# IR.net
KiCad netlist of a schematic drawn in Altium Designer
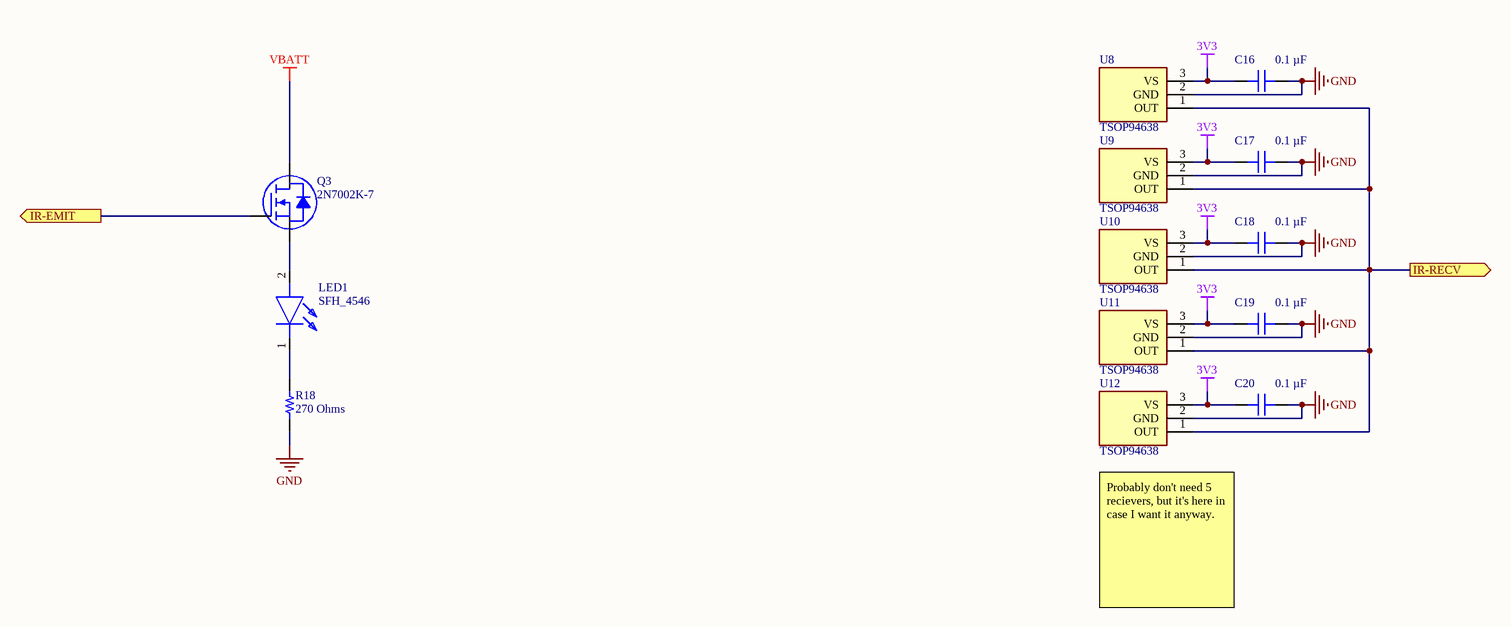
[diagram p0: IR.SchDoc]

(export (version "E")
  (design (tool "Eeschema 10.0.6"))
  (components
    (comp (ref "C16")
      (value "0.1 µF")
      (footprint "CAP 0805_2012")
      (description "CAP CER 0.1UF 25V X7R 0805")
      (fields
        (field (name "PART NUMBER") "0805B104K250CT")
        (field (name "CAPACITANCE") "0.1 µF")
        (field (name "MANUFACTURER") "Walsin Technology Corporation")
      )
      (libsource (lib "dblib") (part "Capacitor"))
    )
    (comp (ref "C17")
      (value "0.1 µF")
      (footprint "CAP 0805_2012")
      (description "CAP CER 0.1UF 25V X7R 0805")
      (fields
        (field (name "PART NUMBER") "0805B104K250CT")
        (field (name "CAPACITANCE") "0.1 µF")
        (field (name "MANUFACTURER") "Walsin Technology Corporation")
      )
      (libsource (lib "dblib") (part "Capacitor"))
    )
    (comp (ref "C18")
      (value "0.1 µF")
      (footprint "CAP 0805_2012")
      (description "CAP CER 0.1UF 25V X7R 0805")
      (fields
        (field (name "PART NUMBER") "0805B104K250CT")
        (field (name "CAPACITANCE") "0.1 µF")
        (field (name "MANUFACTURER") "Walsin Technology Corporation")
      )
      (libsource (lib "dblib") (part "Capacitor"))
    )
    (comp (ref "C19")
      (value "0.1 µF")
      (footprint "CAP 0805_2012")
      (description "CAP CER 0.1UF 25V X7R 0805")
      (fields
        (field (name "PART NUMBER") "0805B104K250CT")
        (field (name "CAPACITANCE") "0.1 µF")
        (field (name "MANUFACTURER") "Walsin Technology Corporation")
      )
      (libsource (lib "dblib") (part "Capacitor"))
    )
    (comp (ref "C20")
      (value "0.1 µF")
      (footprint "CAP 0805_2012")
      (description "CAP CER 0.1UF 25V X7R 0805")
      (fields
        (field (name "PART NUMBER") "0805B104K250CT")
        (field (name "CAPACITANCE") "0.1 µF")
        (field (name "MANUFACTURER") "Walsin Technology Corporation")
      )
      (libsource (lib "dblib") (part "Capacitor"))
    )
    (comp (ref "LED1")
      (value "SFH_4546")
      (footprint "SamacSys:SFH_4556P")
      (description "LED")
      (fields
        (field (name "MANUFACTURER_PART_NUMBER") "SFH 4546")
        (field (name "MOUSER PART NUMBER") "720-SFH4546")
      )
      (libsource (lib "*") (part "SFH_4546"))
    )
    (comp (ref "Q3")
      (value "2N7002K-7")
      (footprint "DIODES SOT-23-3")
      (description "MOSFET N-CH 60V 380MA SOT23-3")
      (fields (field (name "MANUFACTURER") "Diodes Incorporated"))
      (libsource (lib "dblib") (part "DIODES INC MOSFET N-CH SOT-23-3"))
    )
    (comp (ref "R18")
      (value "270 Ohms")
      (footprint "RES 0805_2012")
      (description "RES SMD 270 OHM 1% 1/8W 0805")
      (fields
        (field (name "PART NUMBER") "CRG0805F270R")
        (field (name "MANUFACTURER") "TE Connectivity Passive Product")
      )
      (libsource (lib "dblib") (part "Resistor"))
    )
    (comp (ref "U8")
      (value "TSOP94638")
      (footprint "SamacSys:TSOP94638")
      (description "Integrated Circuit")
      (fields (field (name "MOUSER PART NUMBER") "78-TSOP94638"))
      (libsource (lib "*") (part "TSOP94638"))
    )
    (comp (ref "U9")
      (value "TSOP94638")
      (footprint "SamacSys:TSOP94638")
      (description "Integrated Circuit")
      (fields (field (name "MOUSER PART NUMBER") "78-TSOP94638"))
      (libsource (lib "*") (part "TSOP94638"))
    )
    (comp (ref "U10")
      (value "TSOP94638")
      (footprint "SamacSys:TSOP94638")
      (description "Integrated Circuit")
      (fields (field (name "MOUSER PART NUMBER") "78-TSOP94638"))
      (libsource (lib "*") (part "TSOP94638"))
    )
    (comp (ref "U11")
      (value "TSOP94638")
      (footprint "SamacSys:TSOP94638")
      (description "Integrated Circuit")
      (fields (field (name "MOUSER PART NUMBER") "78-TSOP94638"))
      (libsource (lib "*") (part "TSOP94638"))
    )
    (comp (ref "U12")
      (value "TSOP94638")
      (footprint "SamacSys:TSOP94638")
      (description "Integrated Circuit")
      (fields (field (name "MOUSER PART NUMBER") "78-TSOP94638"))
      (libsource (lib "*") (part "TSOP94638"))
    )
  )
  (nets
    (net (code "1") (name "/IR-EMIT") (class "Default")
      (node (ref "Q3") (pin "1") (pinfunction "G_1") (pintype "passive"))
    )
    (net (code "2") (name "/IR-RECV") (class "Default")
      (node (ref "U10") (pin "1") (pinfunction "OUT_1") (pintype "passive"))
      (node (ref "U11") (pin "1") (pinfunction "OUT_1") (pintype "passive"))
      (node (ref "U12") (pin "1") (pinfunction "OUT_1") (pintype "passive"))
      (node (ref "U8") (pin "1") (pinfunction "OUT_1") (pintype "passive"))
      (node (ref "U9") (pin "1") (pinfunction "OUT_1") (pintype "passive"))
    )
    (net (code "3") (name "3V3") (class "Default")
      (node (ref "C16") (pin "2") (pinfunction "2_2") (pintype "passive"))
      (node (ref "C17") (pin "2") (pinfunction "2_2") (pintype "passive"))
      (node (ref "C18") (pin "2") (pinfunction "2_2") (pintype "passive"))
      (node (ref "C19") (pin "2") (pinfunction "2_2") (pintype "passive"))
      (node (ref "C20") (pin "2") (pinfunction "2_2") (pintype "passive"))
      (node (ref "U10") (pin "3") (pinfunction "VS_3") (pintype "passive"))
      (node (ref "U11") (pin "3") (pinfunction "VS_3") (pintype "passive"))
      (node (ref "U12") (pin "3") (pinfunction "VS_3") (pintype "passive"))
      (node (ref "U8") (pin "3") (pinfunction "VS_3") (pintype "passive"))
      (node (ref "U9") (pin "3") (pinfunction "VS_3") (pintype "passive"))
    )
    (net (code "4") (name "GND") (class "Default")
      (node (ref "C16") (pin "1") (pinfunction "1_1") (pintype "passive"))
      (node (ref "C17") (pin "1") (pinfunction "1_1") (pintype "passive"))
      (node (ref "C18") (pin "1") (pinfunction "1_1") (pintype "passive"))
      (node (ref "C19") (pin "1") (pinfunction "1_1") (pintype "passive"))
      (node (ref "C20") (pin "1") (pinfunction "1_1") (pintype "passive"))
      (node (ref "R18") (pin "1") (pinfunction "1_1") (pintype "passive"))
      (node (ref "U10") (pin "2") (pinfunction "GND_2") (pintype "passive"))
      (node (ref "U11") (pin "2") (pinfunction "GND_2") (pintype "passive"))
      (node (ref "U12") (pin "2") (pinfunction "GND_2") (pintype "passive"))
      (node (ref "U8") (pin "2") (pinfunction "GND_2") (pintype "passive"))
      (node (ref "U9") (pin "2") (pinfunction "GND_2") (pintype "passive"))
    )
    (net (code "5") (name "Net-(LED1-A)") (class "Default")
      (node (ref "LED1") (pin "2") (pinfunction "A_2") (pintype "passive"))
      (node (ref "Q3") (pin "2") (pinfunction "S_2") (pintype "passive"))
    )
    (net (code "6") (name "Net-(LED1-K)") (class "Default")
      (node (ref "LED1") (pin "1") (pinfunction "K_1") (pintype "passive"))
      (node (ref "R18") (pin "2") (pinfunction "2_2") (pintype "passive"))
    )
    (net (code "7") (name "VBATT") (class "Default")
      (node (ref "Q3") (pin "3") (pinfunction "D_3") (pintype "passive"))
    )
  )
)
